# LEDs_and_Buttons.net
KiCad netlist of a schematic drawn in EAGLE
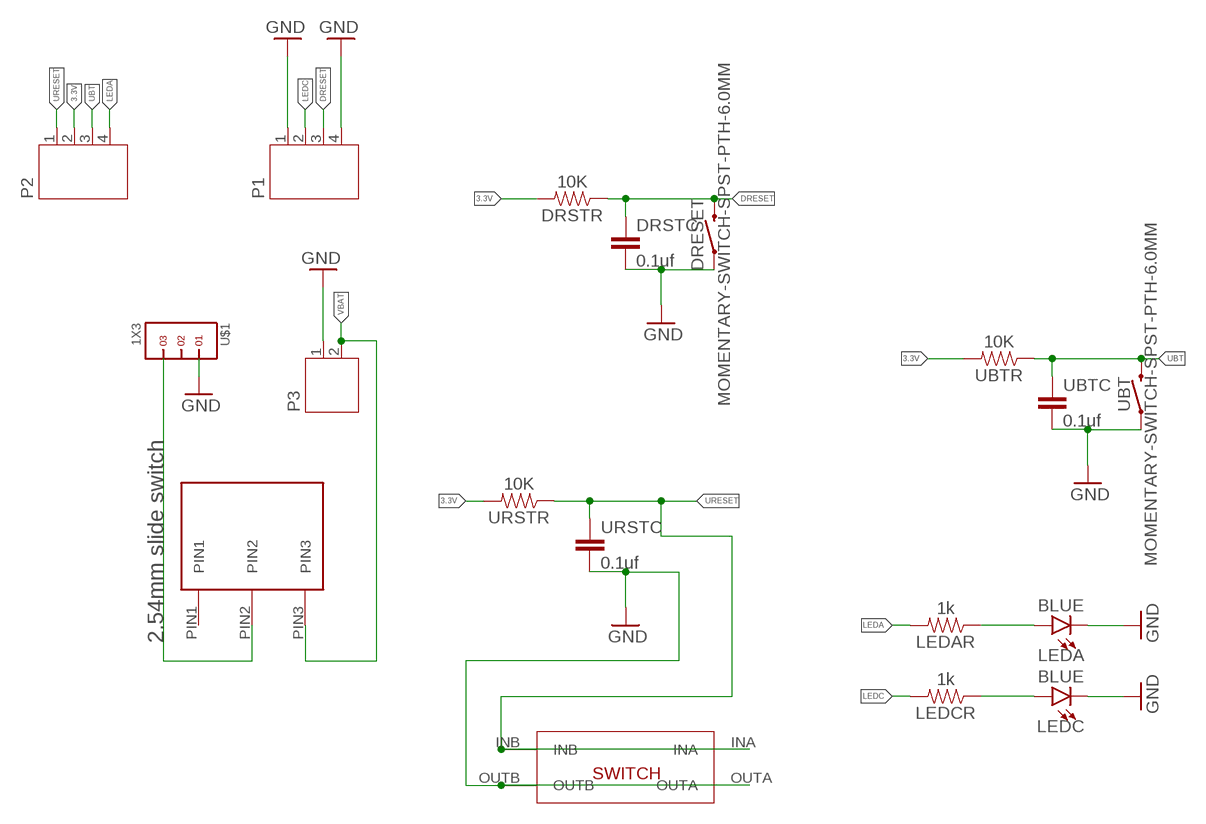
[diagram p0: schematic, sheet 1]

(export (version "E")
  (design (tool "Eeschema 10.0.6"))
  (components
    (comp (ref "DRESET")
      (value "MOMENTARY-SWITCH-SPST-PTH-6.0MM")
      (footprint "eagle-import:TACTILE_SWITCH_PTH_6.0MM")
      (libsource (lib "eagle-import") (part "MOMENTARY-SWITCH-SPST-PTH-6.0MM"))
    )
    (comp (ref "DRSTC")
      (value "0.1uf")
      (footprint "eagle-import:0805")
      (libsource (lib "eagle-import") (part "22UF-0805-6.3V-20%"))
    )
    (comp (ref "DRSTR")
      (value "10K")
      (footprint "eagle-import:0805")
      (libsource (lib "eagle-import") (part "0.75OHM-0805-1/4W-1%"))
    )
    (comp (ref "LEDA")
      (value "BLUE")
      (footprint "eagle-import:LED-1206")
      (libsource (lib "eagle-import") (part "LED-BLUE1206"))
    )
    (comp (ref "LEDAR")
      (value "1k")
      (footprint "eagle-import:0805")
      (libsource (lib "eagle-import") (part "0.75OHM-0805-1/4W-1%"))
    )
    (comp (ref "LEDC")
      (value "BLUE")
      (footprint "eagle-import:LED-1206")
      (libsource (lib "eagle-import") (part "LED-BLUE1206"))
    )
    (comp (ref "LEDCR")
      (value "1k")
      (footprint "eagle-import:0805")
      (libsource (lib "eagle-import") (part "0.75OHM-0805-1/4W-1%"))
    )
    (comp (ref "P1")
      (value "JST-PH4")
      (footprint "eagle-import:JST-PH4")
      (libsource (lib "eagle-import") (part "JST-PH4"))
    )
    (comp (ref "P2")
      (value "JST-PH4")
      (footprint "eagle-import:JST-PH4")
      (libsource (lib "eagle-import") (part "JST-PH4"))
    )
    (comp (ref "P3")
      (value "JST-PH2")
      (footprint "eagle-import:JST-PH2")
      (libsource (lib "eagle-import") (part "JST-PH2"))
    )
    (comp (ref "U$1")
      (value "1X3")
      (footprint "eagle-import:1X3")
      (libsource (lib "eagle-import") (part "1X3"))
    )
    (comp (ref "U$2")
      (value "4X4X1.5_SMD_SWITCH")
      (footprint "eagle-import:4X4X1.5_SMD_SWITCH")
      (libsource (lib "eagle-import") (part "4X4X1.5_SMD_SWITCH"))
    )
    (comp (ref "U$14")
      (value "TS02_SWITCH")
      (footprint "eagle-import:TS02_SWITCH")
      (libsource (lib "eagle-import") (part "TS02_SWITCH"))
    )
    (comp (ref "UBT")
      (value "MOMENTARY-SWITCH-SPST-PTH-6.0MM")
      (footprint "eagle-import:TACTILE_SWITCH_PTH_6.0MM")
      (libsource (lib "eagle-import") (part "MOMENTARY-SWITCH-SPST-PTH-6.0MM"))
    )
    (comp (ref "UBTC")
      (value "0.1uf")
      (footprint "eagle-import:0805")
      (libsource (lib "eagle-import") (part "22UF-0805-6.3V-20%"))
    )
    (comp (ref "UBTR")
      (value "10K")
      (footprint "eagle-import:0805")
      (libsource (lib "eagle-import") (part "0.75OHM-0805-1/4W-1%"))
    )
    (comp (ref "URSTC")
      (value "0.1uf")
      (footprint "eagle-import:0805")
      (libsource (lib "eagle-import") (part "22UF-0805-6.3V-20%"))
    )
    (comp (ref "URSTR")
      (value "10K")
      (footprint "eagle-import:0805")
      (libsource (lib "eagle-import") (part "0.75OHM-0805-1/4W-1%"))
    )
  )
  (nets
    (net (code "1") (name "3.3V") (class "Default")
      (node (ref "DRSTR") (pin "2") (pinfunction "2_2") (pintype "passive"))
      (node (ref "P2") (pin "2") (pinfunction "2_2") (pintype "passive"))
      (node (ref "UBTR") (pin "2") (pinfunction "2_2") (pintype "passive"))
      (node (ref "URSTR") (pin "2") (pinfunction "2_2") (pintype "passive"))
    )
    (net (code "2") (name "DRESET") (class "Default")
      (node (ref "DRESET") (pin "3") (pinfunction "2_3") (pintype "passive"))
      (node (ref "DRSTC") (pin "1") (pinfunction "1_1") (pintype "passive"))
      (node (ref "DRSTR") (pin "1") (pinfunction "1_1") (pintype "passive"))
      (node (ref "P1") (pin "3") (pinfunction "3_3") (pintype "passive"))
    )
    (net (code "3") (name "GND") (class "Default")
      (node (ref "DRESET") (pin "1") (pinfunction "1_1") (pintype "passive"))
      (node (ref "DRSTC") (pin "2") (pinfunction "2_2") (pintype "passive"))
      (node (ref "LEDA") (pin "C") (pinfunction "C_C") (pintype "passive"))
      (node (ref "LEDC") (pin "C") (pinfunction "C_C") (pintype "passive"))
      (node (ref "P1") (pin "1") (pinfunction "1_1") (pintype "passive"))
      (node (ref "P1") (pin "4") (pinfunction "4_4") (pintype "passive"))
      (node (ref "P3") (pin "1") (pinfunction "1_1") (pintype "passive"))
      (node (ref "U$1") (pin "1") (pinfunction "1_1") (pintype "bidirectional"))
      (node (ref "U$2") (pin "OUTA") (pinfunction "OUTA_OUTA") (pintype "bidirectional"))
      (node (ref "U$2") (pin "OUTB") (pinfunction "OUTB_OUTB") (pintype "bidirectional"))
      (node (ref "UBT") (pin "1") (pinfunction "1_1") (pintype "passive"))
      (node (ref "UBTC") (pin "2") (pinfunction "2_2") (pintype "passive"))
      (node (ref "URSTC") (pin "2") (pinfunction "2_2") (pintype "passive"))
    )
    (net (code "4") (name "LEDA") (class "Default")
      (node (ref "LEDAR") (pin "2") (pinfunction "2_2") (pintype "passive"))
      (node (ref "P2") (pin "4") (pinfunction "4_4") (pintype "passive"))
    )
    (net (code "5") (name "LEDC") (class "Default")
      (node (ref "LEDCR") (pin "2") (pinfunction "2_2") (pintype "passive"))
      (node (ref "P1") (pin "2") (pinfunction "2_2") (pintype "passive"))
    )
    (net (code "6") (name "Net-(LEDA-PadA)") (class "Default")
      (node (ref "LEDA") (pin "A") (pinfunction "A_A") (pintype "passive"))
      (node (ref "LEDAR") (pin "1") (pinfunction "1_1") (pintype "passive"))
    )
    (net (code "7") (name "Net-(LEDC-PadA)") (class "Default")
      (node (ref "LEDC") (pin "A") (pinfunction "A_A") (pintype "passive"))
      (node (ref "LEDCR") (pin "1") (pinfunction "1_1") (pintype "passive"))
    )
    (net (code "8") (name "Net-(U$1-Pad3)") (class "Default")
      (node (ref "U$1") (pin "3") (pinfunction "3_3") (pintype "bidirectional"))
      (node (ref "U$14") (pin "PIN2") (pinfunction "PIN2_PIN2") (pintype "bidirectional"))
    )
    (net (code "9") (name "UBT") (class "Default")
      (node (ref "P2") (pin "3") (pinfunction "3_3") (pintype "passive"))
      (node (ref "UBT") (pin "3") (pinfunction "2_3") (pintype "passive"))
      (node (ref "UBTC") (pin "1") (pinfunction "1_1") (pintype "passive"))
      (node (ref "UBTR") (pin "1") (pinfunction "1_1") (pintype "passive"))
    )
    (net (code "10") (name "URESET") (class "Default")
      (node (ref "P2") (pin "1") (pinfunction "1_1") (pintype "passive"))
      (node (ref "U$2") (pin "INA") (pinfunction "INA_INA") (pintype "bidirectional"))
      (node (ref "U$2") (pin "INB") (pinfunction "INB_INB") (pintype "bidirectional"))
      (node (ref "URSTC") (pin "1") (pinfunction "1_1") (pintype "passive"))
      (node (ref "URSTR") (pin "1") (pinfunction "1_1") (pintype "passive"))
    )
    (net (code "11") (name "VBAT") (class "Default")
      (node (ref "P3") (pin "2") (pinfunction "2_2") (pintype "passive"))
      (node (ref "U$14") (pin "PIN3") (pinfunction "PIN3_PIN3") (pintype "bidirectional"))
    )
    (net (code "12") (name "unconnected-(U$1-Pad2)") (class "Default")
      (node (ref "U$1") (pin "2") (pinfunction "2_2") (pintype "bidirectional"))
    )
    (net (code "13") (name "unconnected-(U$14-PadPIN1)") (class "Default")
      (node (ref "U$14") (pin "PIN1") (pinfunction "PIN1_PIN1") (pintype "bidirectional"))
    )
  )
)
